# 09_Misc.net
KiCad netlist of a schematic drawn in Altium Designer
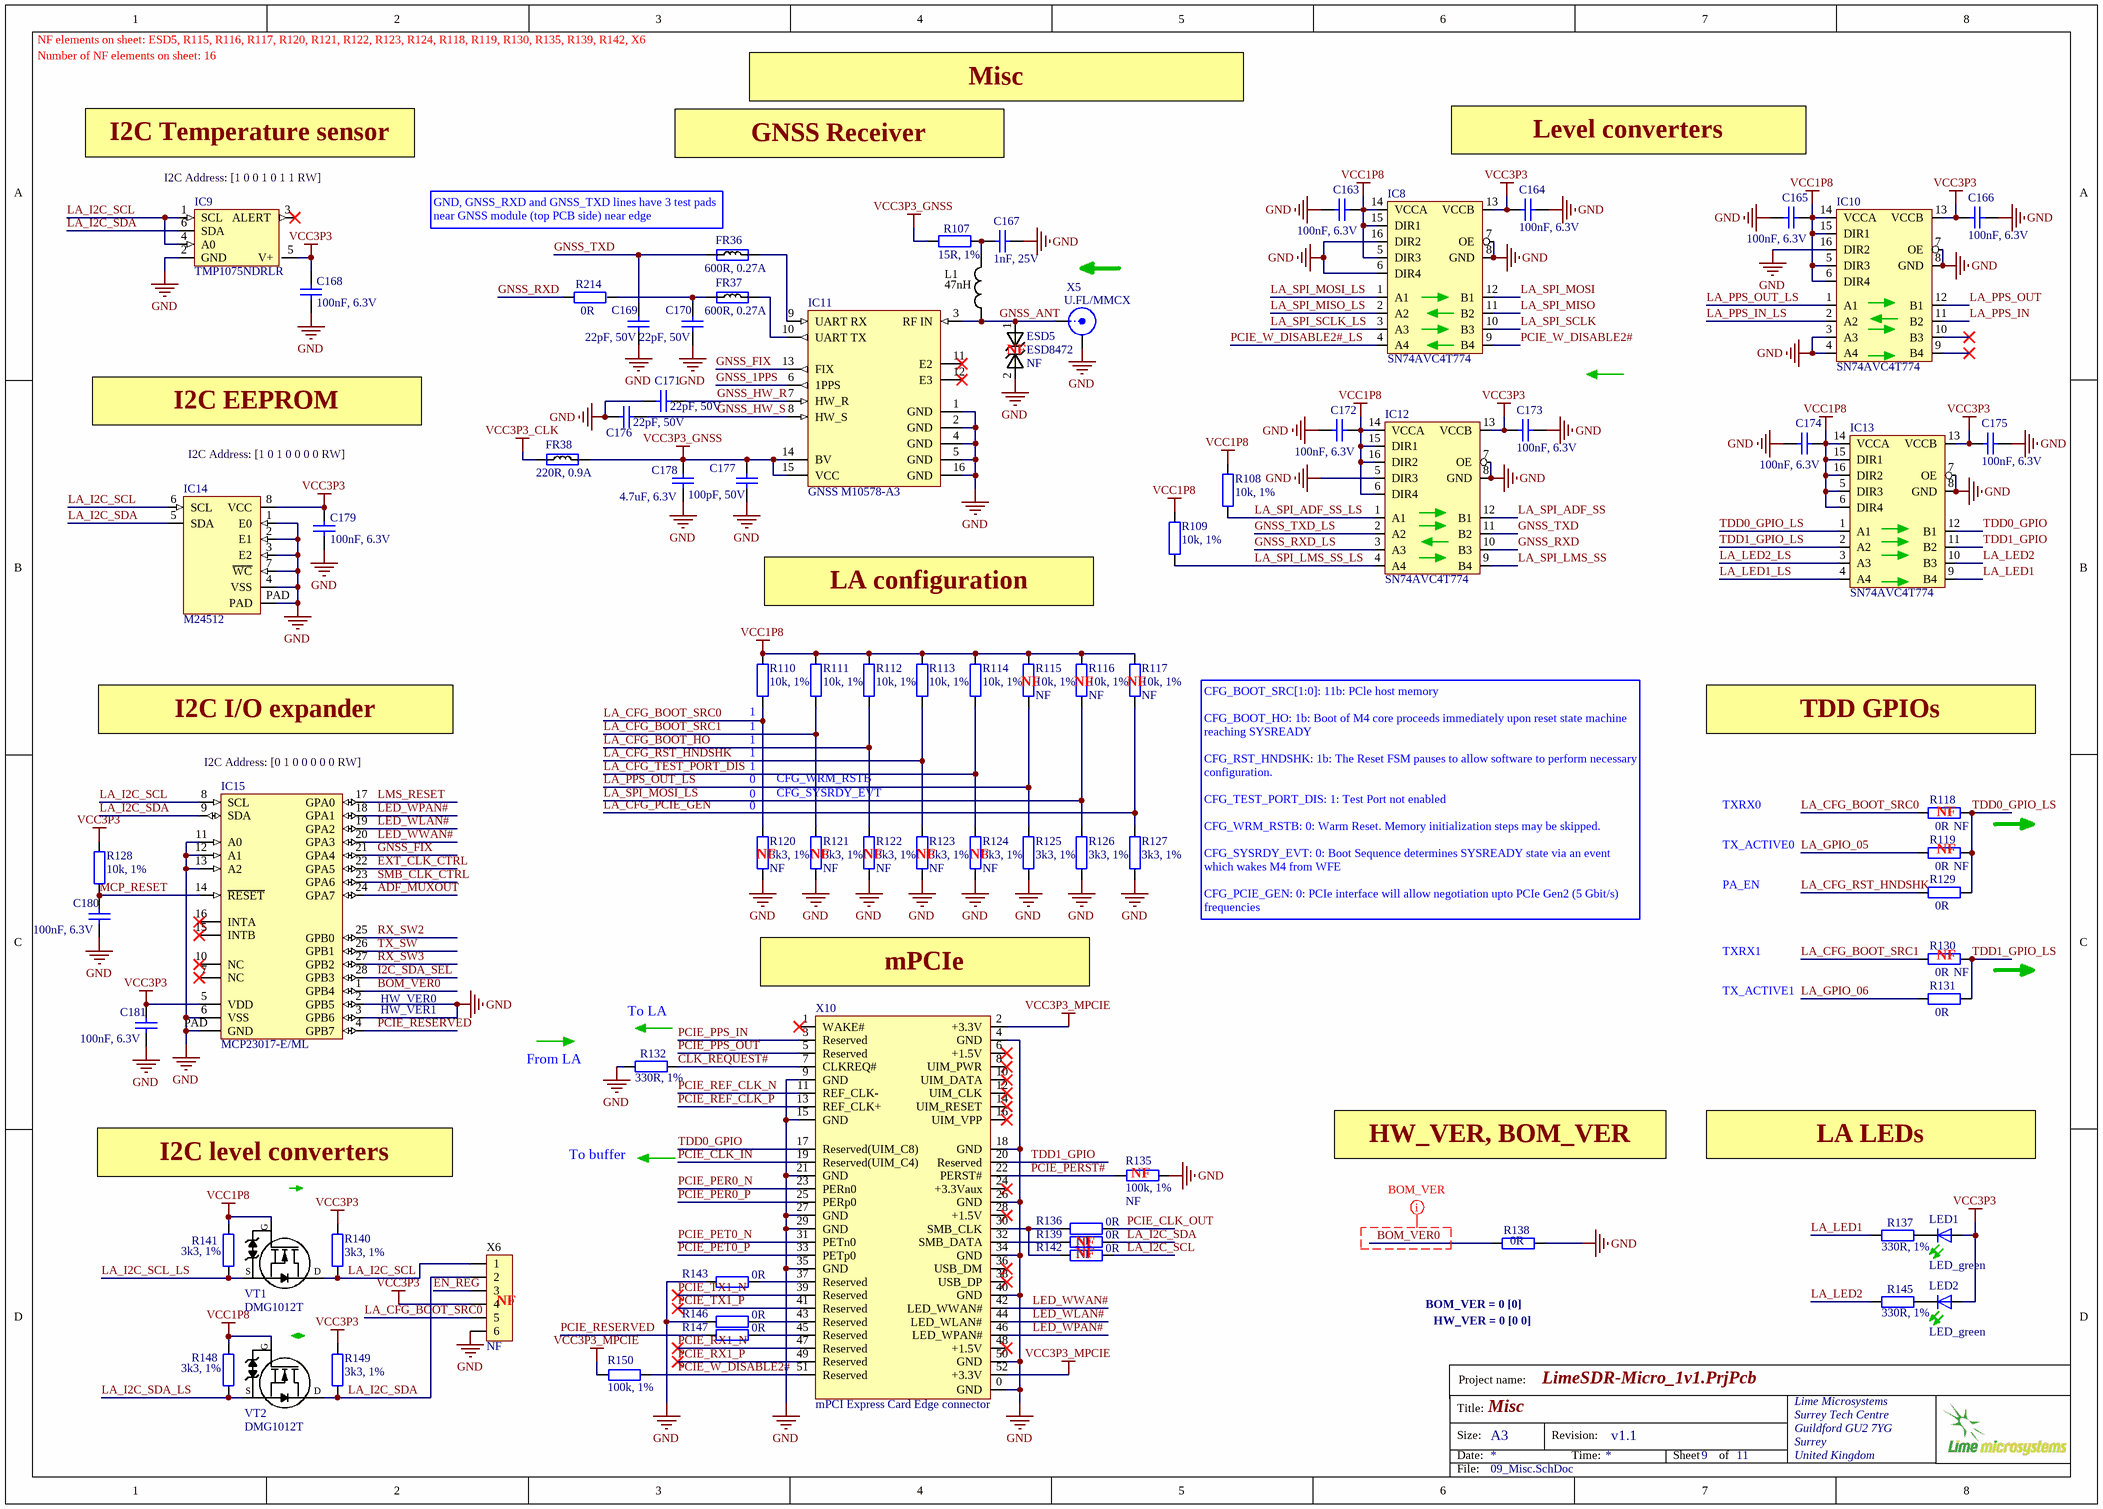
[diagram p0: 09_Misc.SchDoc]

(export (version "E")
  (design (tool "Eeschema 10.0.6"))
  (components
    (comp (ref "C163")
      (value "100nF, 6.3V")
      (footprint "CAP0201")
      (fields (field (name "MANUFACTURER") "Samsung") (field (name "TOLERANCE") "20%"))
      (libsource (lib "LimeMicroAltiumLib_schLib") (part "Cap_0402"))
    )
    (comp (ref "C164")
      (value "100nF, 6.3V")
      (footprint "CAP0201")
      (fields (field (name "MANUFACTURER") "Samsung") (field (name "TOLERANCE") "20%"))
      (libsource (lib "LimeMicroAltiumLib_schLib") (part "Cap_0402"))
    )
    (comp (ref "C165")
      (value "100nF, 6.3V")
      (footprint "CAP0201")
      (fields (field (name "MANUFACTURER") "Samsung") (field (name "TOLERANCE") "20%"))
      (libsource (lib "LimeMicroAltiumLib_schLib") (part "Cap_0402"))
    )
    (comp (ref "C166")
      (value "100nF, 6.3V")
      (footprint "CAP0201")
      (fields (field (name "MANUFACTURER") "Samsung") (field (name "TOLERANCE") "20%"))
      (libsource (lib "LimeMicroAltiumLib_schLib") (part "Cap_0402"))
    )
    (comp (ref "C167")
      (value "1nF, 25V")
      (footprint "CAP0201")
      (fields (field (name "TOLERANCE") "±10%") (field (name "MANUFACTURER") "TDK Corporation"))
      (libsource (lib "LimeMicroAltiumLib_schLib") (part "Cap_0402"))
    )
    (comp (ref "C168")
      (value "100nF, 6.3V")
      (footprint "CAP0201")
      (fields (field (name "MANUFACTURER") "Samsung") (field (name "TOLERANCE") "20%"))
      (libsource (lib "LimeMicroAltiumLib_schLib") (part "Cap_0402"))
    )
    (comp (ref "C169")
      (value "22pF, 50V")
      (footprint "CAP0201")
      (fields
        (field (name "MANUFACTURER") "Murata")
        (field (name "TOLERANCE") "5%")
        (field (name "VOLTAGE") "50V")
      )
      (libsource (lib "LimeMicroAltiumLib_schLib") (part "Cap_0402"))
    )
    (comp (ref "C170")
      (value "22pF, 50V")
      (footprint "CAP0201")
      (fields
        (field (name "MANUFACTURER") "Murata")
        (field (name "TOLERANCE") "5%")
        (field (name "VOLTAGE") "50V")
      )
      (libsource (lib "LimeMicroAltiumLib_schLib") (part "Cap_0402"))
    )
    (comp (ref "C171")
      (value "22pF, 50V")
      (footprint "CAP0201")
      (fields
        (field (name "MANUFACTURER") "Murata")
        (field (name "TOLERANCE") "5%")
        (field (name "VOLTAGE") "50V")
      )
      (libsource (lib "LimeMicroAltiumLib_schLib") (part "Cap_0402"))
    )
    (comp (ref "C172")
      (value "100nF, 6.3V")
      (footprint "CAP0201")
      (fields (field (name "MANUFACTURER") "Samsung") (field (name "TOLERANCE") "20%"))
      (libsource (lib "LimeMicroAltiumLib_schLib") (part "Cap_0402"))
    )
    (comp (ref "C173")
      (value "100nF, 6.3V")
      (footprint "CAP0201")
      (fields (field (name "MANUFACTURER") "Samsung") (field (name "TOLERANCE") "20%"))
      (libsource (lib "LimeMicroAltiumLib_schLib") (part "Cap_0402"))
    )
    (comp (ref "C174")
      (value "100nF, 6.3V")
      (footprint "CAP0201")
      (fields (field (name "MANUFACTURER") "Samsung") (field (name "TOLERANCE") "20%"))
      (libsource (lib "LimeMicroAltiumLib_schLib") (part "Cap_0402"))
    )
    (comp (ref "C175")
      (value "100nF, 6.3V")
      (footprint "CAP0201")
      (fields (field (name "MANUFACTURER") "Samsung") (field (name "TOLERANCE") "20%"))
      (libsource (lib "LimeMicroAltiumLib_schLib") (part "Cap_0402"))
    )
    (comp (ref "C176")
      (value "22pF, 50V")
      (footprint "CAP0201")
      (fields
        (field (name "MANUFACTURER") "Murata")
        (field (name "TOLERANCE") "5%")
        (field (name "VOLTAGE") "50V")
      )
      (libsource (lib "LimeMicroAltiumLib_schLib") (part "Cap_0402"))
    )
    (comp (ref "C177")
      (value "100pF, 50V")
      (footprint "CAP0201")
      (fields
        (field (name "MANUFACTURER") "TDK")
        (field (name "TOLERANCE") "5%")
        (field (name "VOLTAGE") "50V")
      )
      (libsource (lib "LimeMicroAltiumLib_schLib") (part "Cap_0402"))
    )
    (comp (ref "C178")
      (value "4.7uF, 6.3V")
      (footprint "CAP0402")
      (fields
        (field (name "MANUFACTURER") "Murata Electronics North America")
        (field (name "TOLERANCE") "±20%")
      )
      (libsource (lib "LimeMicroAltiumLib_schLib") (part "Cap_0402"))
    )
    (comp (ref "C179")
      (value "100nF, 6.3V")
      (footprint "CAP0201")
      (fields (field (name "MANUFACTURER") "Samsung") (field (name "TOLERANCE") "20%"))
      (libsource (lib "LimeMicroAltiumLib_schLib") (part "Cap_0402"))
    )
    (comp (ref "C180")
      (value "100nF, 6.3V")
      (footprint "CAP0201")
      (fields (field (name "MANUFACTURER") "Samsung") (field (name "TOLERANCE") "20%"))
      (libsource (lib "LimeMicroAltiumLib_schLib") (part "Cap_0402"))
    )
    (comp (ref "C181")
      (value "100nF, 6.3V")
      (footprint "CAP0201")
      (fields (field (name "MANUFACTURER") "Samsung") (field (name "TOLERANCE") "20%"))
      (libsource (lib "LimeMicroAltiumLib_schLib") (part "Cap_0402"))
    )
    (comp (ref "ESD5")
      (value "ESD8472")
      (footprint "ESD8472_X3DFN2")
      (fields (field (name "MANUFACTURER") "ON Semiconductor") (field (name "ASSEMBLY INFO") "NF"))
      (libsource (lib "LimeMicroAltiumLib_schLib") (part "ESD8472"))
    )
    (comp (ref "FR36")
      (value "600R, 0.27A")
      (footprint "RES0201")
      (fields (field (name "MANUFACTURER") "Taiyo Yuden"))
      (libsource (lib "LimeMicroAltiumLib_schLib") (part "Ferrite"))
    )
    (comp (ref "FR37")
      (value "600R, 0.27A")
      (footprint "RES0201")
      (fields (field (name "MANUFACTURER") "Taiyo Yuden"))
      (libsource (lib "LimeMicroAltiumLib_schLib") (part "Ferrite"))
    )
    (comp (ref "FR38")
      (value "220R, 0.9A")
      (footprint "RES0402")
      (fields (field (name "MANUFACTURER") "TDK Corporation"))
      (libsource (lib "LimeFPGAboard_schLib") (part "Ferrite"))
    )
    (comp (ref "IC8")
      (value "SN74AVC4T774")
      (footprint "SN74AVC4T774_v1")
      (fields (field (name "MANUFACTURER") "Texas Instruments"))
      (libsource (lib "LimeMicroAltiumLib") (part "SN74AVC4T774"))
    )
    (comp (ref "IC9")
      (value "TMP1075NDRLR")
      (footprint "TMP1075NDRLR_temperature_sensor_SOT563")
      (fields (field (name "MANUFACTURER") "Texas Instruments"))
      (libsource (lib "LimeMicroAltiumLib_schLib_r04") (part "TMP1075NDRLR_temperature_sensor"))
    )
    (comp (ref "IC10")
      (value "SN74AVC4T774")
      (footprint "SN74AVC4T774_v1")
      (fields (field (name "MANUFACTURER") "Texas Instruments"))
      (libsource (lib "LimeMicroAltiumLib") (part "SN74AVC4T774"))
    )
    (comp (ref "IC11")
      (value "GNSS M10578-A3")
      (footprint "M10578-A3_v2")
      (fields (field (name "MANUFACTURER") "Antenova"))
      (libsource (lib "LimeMicroAltiumLib_schLib_r04") (part "M10578-A3_GPS_GNSS"))
    )
    (comp (ref "IC12")
      (value "SN74AVC4T774")
      (footprint "SN74AVC4T774_v1")
      (fields (field (name "MANUFACTURER") "Texas Instruments"))
      (libsource (lib "LimeMicroAltiumLib") (part "SN74AVC4T774"))
    )
    (comp (ref "IC13")
      (value "SN74AVC4T774")
      (footprint "SN74AVC4T774_v1")
      (fields (field (name "MANUFACTURER") "Texas Instruments"))
      (libsource (lib "LimeMicroAltiumLib") (part "SN74AVC4T774"))
    )
    (comp (ref "IC14")
      (value "M24512")
      (footprint "M24128-DFMC6TG")
      (fields (field (name "MANUFACTURER") "STMicroelectronics"))
      (libsource (lib "LimeMicroAltiumLib_schLib") (part "M24128-DFMC6TG"))
    )
    (comp (ref "IC15")
      (value "MCP23017-E/ML")
      (footprint "MCP23017-E/ML_QFN28")
      (fields (field (name "MANUFACTURER") "Microchip"))
      (libsource (lib "LimeMicroAltiumLib") (part "MCP23017-E/ML_I2C_expander"))
    )
    (comp (ref "L1")
      (value "47nH")
      (footprint "RES0402")
      (fields
        (field (name "MANUFACTURER") "COILCRAFT")
        (field (name "MANUFACTURER PART NUMBER") "0402HP-47NXJLU")
      )
      (libsource (lib "LimeMicroAltiumLib_schLib") (part "Inductor_0603"))
    )
    (comp (ref "LED1")
      (value "LED_green")
      (footprint "LED0201")
      (fields (field (name "MANUFACTURER") "Kingbright"))
      (libsource (lib "LimeFPGAboard_schLib") (part "LED_green"))
    )
    (comp (ref "LED2")
      (value "LED_green")
      (footprint "LED0201")
      (fields (field (name "MANUFACTURER") "Kingbright"))
      (libsource (lib "LimeFPGAboard_schLib") (part "LED_green"))
    )
    (comp (ref "R107")
      (value "15R, 1%")
      (footprint "RES0201")
      (fields (field (name "MANUFACTURER") "Yageo") (field (name "TOLERANCE") "1%"))
      (libsource (lib "LimeFPGAboard_schLib") (part "Res_0402"))
    )
    (comp (ref "R108")
      (value "10k, 1%")
      (footprint "RES0201")
      (fields (field (name "MANUFACTURER") "Yageo") (field (name "TOLERANCE") "1%"))
      (libsource (lib "LimeFPGAboard_schLib") (part "Res_0402"))
    )
    (comp (ref "R109")
      (value "10k, 1%")
      (footprint "RES0201")
      (fields (field (name "MANUFACTURER") "Yageo") (field (name "TOLERANCE") "1%"))
      (libsource (lib "LimeFPGAboard_schLib") (part "Res_0402"))
    )
    (comp (ref "R110")
      (value "10k, 1%")
      (footprint "RES0201")
      (fields (field (name "MANUFACTURER") "Yageo") (field (name "TOLERANCE") "1%"))
      (libsource (lib "LimeFPGAboard_schLib") (part "Res_0402"))
    )
    (comp (ref "R111")
      (value "10k, 1%")
      (footprint "RES0201")
      (fields (field (name "MANUFACTURER") "Yageo") (field (name "TOLERANCE") "1%"))
      (libsource (lib "LimeFPGAboard_schLib") (part "Res_0402"))
    )
    (comp (ref "R112")
      (value "10k, 1%")
      (footprint "RES0201")
      (fields (field (name "MANUFACTURER") "Yageo") (field (name "TOLERANCE") "1%"))
      (libsource (lib "LimeFPGAboard_schLib") (part "Res_0402"))
    )
    (comp (ref "R113")
      (value "10k, 1%")
      (footprint "RES0201")
      (fields (field (name "MANUFACTURER") "Yageo") (field (name "TOLERANCE") "1%"))
      (libsource (lib "LimeFPGAboard_schLib") (part "Res_0402"))
    )
    (comp (ref "R114")
      (value "10k, 1%")
      (footprint "RES0201")
      (fields (field (name "MANUFACTURER") "Yageo") (field (name "TOLERANCE") "1%"))
      (libsource (lib "LimeFPGAboard_schLib") (part "Res_0402"))
    )
    (comp (ref "R115")
      (value "10k, 1%")
      (footprint "RES0201")
      (fields
        (field (name "ASSEMBLY INFO") "NF")
        (field (name "MANUFACTURER") "Yageo")
        (field (name "TOLERANCE") "1%")
      )
      (libsource (lib "LimeFPGAboard_schLib") (part "Res_0402"))
    )
    (comp (ref "R116")
      (value "10k, 1%")
      (footprint "RES0201")
      (fields
        (field (name "ASSEMBLY INFO") "NF")
        (field (name "MANUFACTURER") "Yageo")
        (field (name "TOLERANCE") "1%")
      )
      (libsource (lib "LimeFPGAboard_schLib") (part "Res_0402"))
    )
    (comp (ref "R117")
      (value "10k, 1%")
      (footprint "RES0201")
      (fields
        (field (name "ASSEMBLY INFO") "NF")
        (field (name "MANUFACTURER") "Yageo")
        (field (name "TOLERANCE") "1%")
      )
      (libsource (lib "LimeFPGAboard_schLib") (part "Res_0402"))
    )
    (comp (ref "R118")
      (value "0R")
      (footprint "RES0201")
      (fields
        (field (name "ASSEMBLY INFO") "NF")
        (field (name "MANUFACTURER") "Yageo")
        (field (name "TOLERANCE") "5%")
      )
      (libsource (lib "LimeFPGAboard_schLib") (part "Res_0402"))
    )
    (comp (ref "R119")
      (value "0R")
      (footprint "RES0201")
      (fields
        (field (name "ASSEMBLY INFO") "NF")
        (field (name "MANUFACTURER") "Yageo")
        (field (name "TOLERANCE") "5%")
      )
      (libsource (lib "LimeFPGAboard_schLib") (part "Res_0402"))
    )
    (comp (ref "R120")
      (value "3k3, 1%")
      (footprint "RES0201")
      (fields
        (field (name "ASSEMBLY INFO") "NF")
        (field (name "MANUFACTURER") "Yageo")
        (field (name "TOLERANCE") "1%")
      )
      (libsource (lib "LimeFPGAboard_schLib") (part "Res_0402"))
    )
    (comp (ref "R121")
      (value "3k3, 1%")
      (footprint "RES0201")
      (fields
        (field (name "ASSEMBLY INFO") "NF")
        (field (name "MANUFACTURER") "Yageo")
        (field (name "TOLERANCE") "1%")
      )
      (libsource (lib "LimeFPGAboard_schLib") (part "Res_0402"))
    )
    (comp (ref "R122")
      (value "3k3, 1%")
      (footprint "RES0201")
      (fields
        (field (name "ASSEMBLY INFO") "NF")
        (field (name "MANUFACTURER") "Yageo")
        (field (name "TOLERANCE") "1%")
      )
      (libsource (lib "LimeFPGAboard_schLib") (part "Res_0402"))
    )
    (comp (ref "R123")
      (value "3k3, 1%")
      (footprint "RES0201")
      (fields
        (field (name "ASSEMBLY INFO") "NF")
        (field (name "MANUFACTURER") "Yageo")
        (field (name "TOLERANCE") "1%")
      )
      (libsource (lib "LimeFPGAboard_schLib") (part "Res_0402"))
    )
    (comp (ref "R124")
      (value "3k3, 1%")
      (footprint "RES0201")
      (fields
        (field (name "ASSEMBLY INFO") "NF")
        (field (name "MANUFACTURER") "Yageo")
        (field (name "TOLERANCE") "1%")
      )
      (libsource (lib "LimeFPGAboard_schLib") (part "Res_0402"))
    )
    (comp (ref "R125")
      (value "3k3, 1%")
      (footprint "RES0201")
      (fields (field (name "MANUFACTURER") "Yageo") (field (name "TOLERANCE") "1%"))
      (libsource (lib "LimeFPGAboard_schLib") (part "Res_0402"))
    )
    (comp (ref "R126")
      (value "3k3, 1%")
      (footprint "RES0201")
      (fields (field (name "MANUFACTURER") "Yageo") (field (name "TOLERANCE") "1%"))
      (libsource (lib "LimeFPGAboard_schLib") (part "Res_0402"))
    )
    (comp (ref "R127")
      (value "3k3, 1%")
      (footprint "RES0201")
      (fields (field (name "MANUFACTURER") "Yageo") (field (name "TOLERANCE") "1%"))
      (libsource (lib "LimeFPGAboard_schLib") (part "Res_0402"))
    )
    (comp (ref "R128")
      (value "10k, 1%")
      (footprint "RES0201")
      (fields (field (name "MANUFACTURER") "Yageo") (field (name "TOLERANCE") "1%"))
      (libsource (lib "LimeFPGAboard_schLib") (part "Res_0402"))
    )
    (comp (ref "R129")
      (value "0R")
      (footprint "RES0201")
      (fields (field (name "MANUFACTURER") "Yageo") (field (name "TOLERANCE") "5%"))
      (libsource (lib "LimeFPGAboard_schLib") (part "Res_0402"))
    )
    (comp (ref "R130")
      (value "0R")
      (footprint "RES0201")
      (fields
        (field (name "ASSEMBLY INFO") "NF")
        (field (name "MANUFACTURER") "Yageo")
        (field (name "TOLERANCE") "5%")
      )
      (libsource (lib "LimeFPGAboard_schLib") (part "Res_0402"))
    )
    (comp (ref "R131")
      (value "0R")
      (footprint "RES0201")
      (fields (field (name "MANUFACTURER") "Yageo") (field (name "TOLERANCE") "5%"))
      (libsource (lib "LimeFPGAboard_schLib") (part "Res_0402"))
    )
    (comp (ref "R132")
      (value "330R, 1%")
      (footprint "RES0201")
      (fields (field (name "MANUFACTURER") "Vishay Dale") (field (name "TOLERANCE") "1%"))
      (libsource (lib "LimeFPGAboard_schLib") (part "Res_0402"))
    )
    (comp (ref "R135")
      (value "100k, 1%")
      (footprint "RES0201")
      (fields
        (field (name "ASSEMBLY INFO") "NF")
        (field (name "MANUFACTURER") "Yageo")
        (field (name "TOLERANCE") "1%")
      )
      (libsource (lib "LimeMicroAltiumLib_schLib") (part "Res_0402"))
    )
    (comp (ref "R136")
      (value "0R")
      (footprint "RES0201")
      (fields (field (name "MANUFACTURER") "Yageo") (field (name "TOLERANCE") "5%"))
      (libsource (lib "LimeFPGAboard_schLib") (part "Res_0402"))
    )
    (comp (ref "R137")
      (value "330R, 1%")
      (footprint "RES0201")
      (fields (field (name "MANUFACTURER") "Vishay Dale") (field (name "TOLERANCE") "1%"))
      (libsource (lib "LimeFPGAboard_schLib") (part "Res_0402"))
    )
    (comp (ref "R138")
      (value "0R")
      (footprint "RES0201")
      (fields (field (name "MANUFACTURER") "Yageo") (field (name "TOLERANCE") "5%"))
      (libsource (lib "LimeFPGAboard_schLib") (part "Res_0402"))
    )
    (comp (ref "R139")
      (value "0R")
      (footprint "RES0201")
      (fields
        (field (name "ASSEMBLY INFO") "NF")
        (field (name "MANUFACTURER") "Yageo")
        (field (name "TOLERANCE") "5%")
      )
      (libsource (lib "LimeFPGAboard_schLib") (part "Res_0402"))
    )
    (comp (ref "R140")
      (value "3k3, 1%")
      (footprint "RES0201")
      (fields (field (name "MANUFACTURER") "Yageo") (field (name "TOLERANCE") "1%"))
      (libsource (lib "LimeFPGAboard_schLib") (part "Res_0402"))
    )
    (comp (ref "R141")
      (value "3k3, 1%")
      (footprint "RES0201")
      (fields (field (name "MANUFACTURER") "Yageo") (field (name "TOLERANCE") "1%"))
      (libsource (lib "LimeFPGAboard_schLib") (part "Res_0402"))
    )
    (comp (ref "R142")
      (value "0R")
      (footprint "RES0201")
      (fields
        (field (name "ASSEMBLY INFO") "NF")
        (field (name "MANUFACTURER") "Yageo")
        (field (name "TOLERANCE") "5%")
      )
      (libsource (lib "LimeFPGAboard_schLib") (part "Res_0402"))
    )
    (comp (ref "R143")
      (value "0R")
      (footprint "RES0201")
      (fields (field (name "MANUFACTURER") "Yageo") (field (name "TOLERANCE") "5%"))
      (libsource (lib "LimeFPGAboard_schLib") (part "Res_0402"))
    )
    (comp (ref "R145")
      (value "330R, 1%")
      (footprint "RES0201")
      (fields (field (name "MANUFACTURER") "Vishay Dale") (field (name "TOLERANCE") "1%"))
      (libsource (lib "LimeFPGAboard_schLib") (part "Res_0402"))
    )
    (comp (ref "R146")
      (value "0R")
      (footprint "RES0201")
      (fields (field (name "MANUFACTURER") "Yageo") (field (name "TOLERANCE") "5%"))
      (libsource (lib "LimeFPGAboard_schLib") (part "Res_0402"))
    )
    (comp (ref "R147")
      (value "0R")
      (footprint "RES0201")
      (fields (field (name "MANUFACTURER") "Yageo") (field (name "TOLERANCE") "5%"))
      (libsource (lib "LimeFPGAboard_schLib") (part "Res_0402"))
    )
    (comp (ref "R148")
      (value "3k3, 1%")
      (footprint "RES0201")
      (fields (field (name "MANUFACTURER") "Yageo") (field (name "TOLERANCE") "1%"))
      (libsource (lib "LimeFPGAboard_schLib") (part "Res_0402"))
    )
    (comp (ref "R149")
      (value "3k3, 1%")
      (footprint "RES0201")
      (fields (field (name "MANUFACTURER") "Yageo") (field (name "TOLERANCE") "1%"))
      (libsource (lib "LimeFPGAboard_schLib") (part "Res_0402"))
    )
    (comp (ref "R150")
      (value "100k, 1%")
      (footprint "RES0201")
      (fields (field (name "MANUFACTURER") "Yageo") (field (name "TOLERANCE") "1%"))
      (libsource (lib "LimeMicroAltiumLib_schLib") (part "Res_0402"))
    )
    (comp (ref "R214")
      (value "0R")
      (footprint "RES0201")
      (fields (field (name "MANUFACTURER") "Yageo") (field (name "TOLERANCE") "5%"))
      (libsource (lib "LimeFPGAboard_schLib") (part "Res_0402"))
    )
    (comp (ref "VT1")
      (value "DMG1012T")
      (footprint "SOT523")
      (fields (field (name "MANUFACTURER") "Diodes Incorporated"))
      (libsource (lib "LimeMicroAltiumLib_schLib_r01") (part "DMG1012T"))
    )
    (comp (ref "VT2")
      (value "DMG1012T")
      (footprint "SOT523")
      (fields (field (name "MANUFACTURER") "Diodes Incorporated"))
      (libsource (lib "LimeMicroAltiumLib_schLib_r01") (part "DMG1012T"))
    )
    (comp (ref "X5")
      (value "U.FL/MMCX")
      (footprint "MMCX_UFL_conn_u_v2")
      (description "CONN UMC RCPT STR 50 OHM SMD")
      (fields (field (name "MANUFACTURER") "Molex, LLC"))
      (libsource (lib "LimeMicroAltiumLib_schLib") (part "RF_IF_connector"))
    )
    (comp (ref "X6")
      (value "Molex 0788641001")
      (footprint "Molex_0788641001_spring_contacts")
      (description "Header, 6-pin")
      (fields (field (name "MANUFACTURER") "Molex") (field (name "ASSEMBLY INFO") "NF"))
      (libsource (lib "LimeMicroAltiumLib_schLib_r04") (part "Molex_0788641001_spring_contacts"))
    )
    (comp (ref "X10")
      (value "mPCI Express Card Edge connector")
      (footprint "PCIe_MiniCard")
      (description "PCIe MiniCard full or half size")
      (libsource (lib "LimeMicroAltiumLib_schLib_r04") (part "PCIe_MiniCard_fingers"))
    )
  )
  (nets
    (net (code "1") (name "/ADF_MUXOUT") (class "Default")
      (node (ref "IC15") (pin "24") (pinfunction "GPA7_24") (pintype "bidirectional"))
    )
    (net (code "2") (name "/BOM_VER0") (class "Default")
      (node (ref "IC15") (pin "1") (pinfunction "GPB4_1") (pintype "bidirectional"))
      (node (ref "R138") (pin "1") (pinfunction "1_1") (pintype "passive"))
    )
    (net (code "3") (name "/CLK_REQUEST#") (class "Default")
      (node (ref "R132") (pin "1") (pinfunction "1_1") (pintype "passive"))
      (node (ref "X10") (pin "7") (pinfunction "CLKREQ#_7") (pintype "passive"))
    )
    (net (code "4") (name "/EN_REG") (class "Default")
      (node (ref "X6") (pin "3") (pinfunction "3_3") (pintype "passive"))
    )
    (net (code "5") (name "/EXT_CLK_CTRL") (class "Default")
      (node (ref "IC15") (pin "22") (pinfunction "GPA5_22") (pintype "bidirectional"))
    )
    (net (code "6") (name "/GNSS_1PPS") (class "Default")
      (node (ref "IC11") (pin "6") (pinfunction "1PPS_6") (pintype "output"))
    )
    (net (code "7") (name "/GNSS_ANT") (class "Default")
      (node (ref "ESD5") (pin "1") (pinfunction "1_1") (pintype "passive"))
      (node (ref "IC11") (pin "3") (pinfunction "RF_IN_3") (pintype "input"))
      (node (ref "L1") (pin "1") (pinfunction "1_1") (pintype "passive"))
      (node (ref "X5") (pin "1") (pinfunction "X_1") (pintype "passive"))
    )
    (net (code "8") (name "/GNSS_FIX") (class "Default")
      (node (ref "IC11") (pin "13") (pinfunction "FIX_13") (pintype "output"))
      (node (ref "IC15") (pin "21") (pinfunction "GPA4_21") (pintype "bidirectional"))
    )
    (net (code "9") (name "/GNSS_HW_R") (class "Default")
      (node (ref "C171") (pin "1") (pinfunction "1_1") (pintype "passive"))
      (node (ref "IC11") (pin "7") (pinfunction "HW_R_7") (pintype "input"))
    )
    (net (code "10") (name "/GNSS_HW_S") (class "Default")
      (node (ref "C176") (pin "1") (pinfunction "1_1") (pintype "passive"))
      (node (ref "IC11") (pin "8") (pinfunction "HW_S_8") (pintype "input"))
    )
    (net (code "11") (name "/GNSS_RXD") (class "Default")
      (node (ref "IC12") (pin "10") (pinfunction "B3_10") (pintype "passive"))
      (node (ref "R214") (pin "1") (pinfunction "1_1") (pintype "passive"))
    )
    (net (code "12") (name "/GNSS_RXD_LS") (class "Default")
      (node (ref "IC12") (pin "3") (pinfunction "A3_3") (pintype "passive"))
    )
    (net (code "13") (name "/GNSS_TXD") (class "Default")
      (node (ref "C169") (pin "1") (pinfunction "1_1") (pintype "passive"))
      (node (ref "FR36") (pin "1") (pinfunction "1_1") (pintype "passive"))
      (node (ref "IC12") (pin "11") (pinfunction "B2_11") (pintype "passive"))
    )
    (net (code "14") (name "/GNSS_TXD_LS") (class "Default")
      (node (ref "IC12") (pin "2") (pinfunction "A2_2") (pintype "passive"))
    )
    (net (code "15") (name "/I2C_SDA_SEL") (class "Default")
      (node (ref "IC15") (pin "28") (pinfunction "GPB3_28") (pintype "bidirectional"))
    )
    (net (code "16") (name "/LA_CFG_BOOT_HO") (class "Default")
      (node (ref "R112") (pin "2") (pinfunction "2_2") (pintype "passive"))
      (node (ref "R122") (pin "1") (pinfunction "1_1") (pintype "passive"))
    )
    (net (code "17") (name "/LA_CFG_BOOT_SRC0") (class "Default")
      (node (ref "R110") (pin "2") (pinfunction "2_2") (pintype "passive"))
      (node (ref "R118") (pin "1") (pinfunction "1_1") (pintype "passive"))
      (node (ref "R120") (pin "1") (pinfunction "1_1") (pintype "passive"))
      (node (ref "X6") (pin "5") (pinfunction "5_5") (pintype "passive"))
    )
    (net (code "18") (name "/LA_CFG_BOOT_SRC1") (class "Default")
      (node (ref "R111") (pin "2") (pinfunction "2_2") (pintype "passive"))
      (node (ref "R121") (pin "1") (pinfunction "1_1") (pintype "passive"))
      (node (ref "R130") (pin "1") (pinfunction "1_1") (pintype "passive"))
    )
    (net (code "19") (name "/LA_CFG_PCIE_GEN") (class "Default")
      (node (ref "R117") (pin "2") (pinfunction "2_2") (pintype "passive"))
      (node (ref "R127") (pin "1") (pinfunction "1_1") (pintype "passive"))
    )
    (net (code "20") (name "/LA_CFG_RST_HNDSHK") (class "Default")
      (node (ref "R113") (pin "2") (pinfunction "2_2") (pintype "passive"))
      (node (ref "R123") (pin "1") (pinfunction "1_1") (pintype "passive"))
      (node (ref "R129") (pin "1") (pinfunction "1_1") (pintype "passive"))
    )
    (net (code "21") (name "/LA_CFG_TEST_PORT_DIS") (class "Default")
      (node (ref "R114") (pin "2") (pinfunction "2_2") (pintype "passive"))
      (node (ref "R124") (pin "1") (pinfunction "1_1") (pintype "passive"))
    )
    (net (code "22") (name "/LA_GPIO_05") (class "Default")
      (node (ref "R119") (pin "1") (pinfunction "1_1") (pintype "passive"))
    )
    (net (code "23") (name "/LA_GPIO_06") (class "Default")
      (node (ref "R131") (pin "1") (pinfunction "1_1") (pintype "passive"))
    )
    (net (code "24") (name "/LA_I2C_SCL") (class "Default")
      (node (ref "IC14") (pin "6") (pinfunction "SCL_6") (pintype "input"))
      (node (ref "IC15") (pin "8") (pinfunction "SCL_8") (pintype "input"))
      (node (ref "IC9") (pin "1") (pinfunction "SCL_1") (pintype "input"))
      (node (ref "IC9") (pin "4") (pinfunction "A0_4") (pintype "input"))
      (node (ref "R140") (pin "2") (pinfunction "2_2") (pintype "passive"))
      (node (ref "R142") (pin "2") (pinfunction "2_2") (pintype "passive"))
      (node (ref "VT1") (pin "D") (pinfunction "D_D") (pintype "passive"))
      (node (ref "X6") (pin "1") (pinfunction "1_1") (pintype "passive"))
    )
    (net (code "25") (name "/LA_I2C_SCL_LS") (class "Default")
      (node (ref "R141") (pin "2") (pinfunction "2_2") (pintype "passive"))
      (node (ref "VT1") (pin "S") (pinfunction "S_S") (pintype "passive"))
    )
    (net (code "26") (name "/LA_I2C_SDA") (class "Default")
      (node (ref "IC14") (pin "5") (pinfunction "SDA_5") (pintype "bidirectional"))
      (node (ref "IC15") (pin "9") (pinfunction "SDA_9") (pintype "bidirectional"))
      (node (ref "IC9") (pin "6") (pinfunction "SDA_6") (pintype "bidirectional"))
      (node (ref "R139") (pin "2") (pinfunction "2_2") (pintype "passive"))
      (node (ref "R149") (pin "2") (pinfunction "2_2") (pintype "passive"))
      (node (ref "VT2") (pin "D") (pinfunction "D_D") (pintype "passive"))
      (node (ref "X6") (pin "2") (pinfunction "2_2") (pintype "passive"))
    )
    (net (code "27") (name "/LA_I2C_SDA_LS") (class "Default")
      (node (ref "R148") (pin "2") (pinfunction "2_2") (pintype "passive"))
      (node (ref "VT2") (pin "S") (pinfunction "S_S") (pintype "passive"))
    )
    (net (code "28") (name "/LA_LED1") (class "Default")
      (node (ref "IC13") (pin "9") (pinfunction "B4_9") (pintype "passive"))
      (node (ref "R137") (pin "2") (pinfunction "2_2") (pintype "passive"))
    )
    (net (code "29") (name "/LA_LED1_LS") (class "Default")
      (node (ref "IC13") (pin "4") (pinfunction "A4_4") (pintype "passive"))
    )
    (net (code "30") (name "/LA_LED2") (class "Default")
      (node (ref "IC13") (pin "10") (pinfunction "B3_10") (pintype "passive"))
      (node (ref "R145") (pin "2") (pinfunction "2_2") (pintype "passive"))
    )
    (net (code "31") (name "/LA_LED2_LS") (class "Default")
      (node (ref "IC13") (pin "3") (pinfunction "A3_3") (pintype "passive"))
    )
    (net (code "32") (name "/LA_PPS_IN") (class "Default")
      (node (ref "IC10") (pin "11") (pinfunction "B2_11") (pintype "passive"))
    )
    (net (code "33") (name "/LA_PPS_IN_LS") (class "Default")
      (node (ref "IC10") (pin "2") (pinfunction "A2_2") (pintype "passive"))
    )
    (net (code "34") (name "/LA_PPS_OUT") (class "Default")
      (node (ref "IC10") (pin "12") (pinfunction "B1_12") (pintype "passive"))
    )
    (net (code "35") (name "/LA_PPS_OUT_LS") (class "Default")
      (node (ref "IC10") (pin "1") (pinfunction "A1_1") (pintype "passive"))
      (node (ref "R115") (pin "2") (pinfunction "2_2") (pintype "passive"))
      (node (ref "R125") (pin "1") (pinfunction "1_1") (pintype "passive"))
    )
    (net (code "36") (name "/LA_SPI_ADF_SS") (class "Default")
      (node (ref "IC12") (pin "12") (pinfunction "B1_12") (pintype "passive"))
    )
    (net (code "37") (name "/LA_SPI_ADF_SS_LS") (class "Default")
      (node (ref "IC12") (pin "1") (pinfunction "A1_1") (pintype "passive"))
      (node (ref "R108") (pin "2") (pinfunction "2_2") (pintype "passive"))
    )
    (net (code "38") (name "/LA_SPI_LMS_SS") (class "Default")
      (node (ref "IC12") (pin "9") (pinfunction "B4_9") (pintype "passive"))
    )
    (net (code "39") (name "/LA_SPI_LMS_SS_LS") (class "Default")
      (node (ref "IC12") (pin "4") (pinfunction "A4_4") (pintype "passive"))
      (node (ref "R109") (pin "2") (pinfunction "2_2") (pintype "passive"))
    )
    (net (code "40") (name "/LA_SPI_MISO") (class "Default")
      (node (ref "IC8") (pin "11") (pinfunction "B2_11") (pintype "passive"))
    )
    (net (code "41") (name "/LA_SPI_MISO_LS") (class "Default")
      (node (ref "IC8") (pin "2") (pinfunction "A2_2") (pintype "passive"))
    )
    (net (code "42") (name "/LA_SPI_MOSI") (class "Default")
      (node (ref "IC8") (pin "12") (pinfunction "B1_12") (pintype "passive"))
    )
    (net (code "43") (name "/LA_SPI_MOSI_LS") (class "Default")
      (node (ref "IC8") (pin "1") (pinfunction "A1_1") (pintype "passive"))
      (node (ref "R116") (pin "2") (pinfunction "2_2") (pintype "passive"))
      (node (ref "R126") (pin "1") (pinfunction "1_1") (pintype "passive"))
    )
    (net (code "44") (name "/LA_SPI_SCLK") (class "Default")
      (node (ref "IC8") (pin "10") (pinfunction "B3_10") (pintype "passive"))
    )
    (net (code "45") (name "/LA_SPI_SCLK_LS") (class "Default")
      (node (ref "IC8") (pin "3") (pinfunction "A3_3") (pintype "passive"))
    )
    (net (code "46") (name "/LED_WLAN#") (class "Default")
      (node (ref "IC15") (pin "19") (pinfunction "GPA2_19") (pintype "bidirectional"))
      (node (ref "X10") (pin "44") (pinfunction "LED_WLAN#_44") (pintype "passive"))
    )
    (net (code "47") (name "/LED_WPAN#") (class "Default")
      (node (ref "IC15") (pin "18") (pinfunction "GPA1_18") (pintype "bidirectional"))
      (node (ref "X10") (pin "46") (pinfunction "LED_WPAN#_46") (pintype "passive"))
    )
    (net (code "48") (name "/LED_WWAN#") (class "Default")
      (node (ref "IC15") (pin "20") (pinfunction "GPA3_20") (pintype "bidirectional"))
      (node (ref "X10") (pin "42") (pinfunction "LED_WWAN#_42") (pintype "passive"))
    )
    (net (code "49") (name "/LMS_RESET") (class "Default")
      (node (ref "IC15") (pin "17") (pinfunction "GPA0_17") (pintype "bidirectional"))
    )
    (net (code "50") (name "/MCP_RESET") (class "Default")
      (node (ref "C180") (pin "1") (pinfunction "1_1") (pintype "passive"))
      (node (ref "IC15") (pin "14") (pinfunction "~{RESET}_14") (pintype "input"))
      (node (ref "R128") (pin "2") (pinfunction "2_2") (pintype "passive"))
    )
    (net (code "51") (name "/PCIE_CLK_IN") (class "Default")
      (node (ref "X10") (pin "19") (pinfunction "Reserved(UIM_C4)_19") (pintype "passive"))
    )
    (net (code "52") (name "/PCIE_CLK_OUT") (class "Default")
      (node (ref "R136") (pin "2") (pinfunction "2_2") (pintype "passive"))
    )
    (net (code "53") (name "/PCIE_PER0_N") (class "Default")
      (node (ref "X10") (pin "23") (pinfunction "PERn0_23") (pintype "passive"))
    )
    (net (code "54") (name "/PCIE_PER0_P") (class "Default")
      (node (ref "X10") (pin "25") (pinfunction "PERp0_25") (pintype "passive"))
    )
    (net (code "55") (name "/PCIE_PERST#") (class "Default")
      (node (ref "R135") (pin "2") (pinfunction "2_2") (pintype "passive"))
      (node (ref "X10") (pin "22") (pinfunction "PERST#_22") (pintype "passive"))
    )
    (net (code "56") (name "/PCIE_PET0_N") (class "Default")
      (node (ref "X10") (pin "31") (pinfunction "PETn0_31") (pintype "passive"))
    )
    (net (code "57") (name "/PCIE_PET0_P") (class "Default")
      (node (ref "X10") (pin "33") (pinfunction "PETp0_33") (pintype "passive"))
    )
    (net (code "58") (name "/PCIE_PPS_IN") (class "Default")
      (node (ref "X10") (pin "3") (pinfunction "Reserved_3") (pintype "passive"))
    )
    (net (code "59") (name "/PCIE_PPS_OUT") (class "Default")
      (node (ref "X10") (pin "5") (pinfunction "Reserved_5") (pintype "passive"))
    )
    (net (code "60") (name "/PCIE_REF_CLK_N") (class "Default")
      (node (ref "X10") (pin "11") (pinfunction "REF_CLK-_11") (pintype "passive"))
    )
    (net (code "61") (name "/PCIE_REF_CLK_P") (class "Default")
      (node (ref "X10") (pin "13") (pinfunction "REF_CLK+_13") (pintype "passive"))
    )
    (net (code "62") (name "/PCIE_RESERVED") (class "Default")
      (node (ref "IC15") (pin "4") (pinfunction "GPB7_4") (pintype "bidirectional"))
      (node (ref "R147") (pin "1") (pinfunction "1_1") (pintype "passive"))
    )
    (net (code "63") (name "/PCIE_RX1_N") (class "Default")
      (node (ref "X10") (pin "47") (pinfunction "Reserved_47") (pintype "passive+no_connect"))
    )
    (net (code "64") (name "/PCIE_RX1_P") (class "Default")
      (node (ref "X10") (pin "49") (pinfunction "Reserved_49") (pintype "passive+no_connect"))
    )
    (net (code "65") (name "/PCIE_TX1_N") (class "Default")
      (node (ref "X10") (pin "39") (pinfunction "Reserved_39") (pintype "passive+no_connect"))
    )
    (net (code "66") (name "/PCIE_TX1_P") (class "Default")
      (node (ref "X10") (pin "41") (pinfunction "Reserved_41") (pintype "passive+no_connect"))
    )
    (net (code "67") (name "/PCIE_W_DISABLE2#") (class "Default")
      (node (ref "IC8") (pin "9") (pinfunction "B4_9") (pintype "passive"))
      (node (ref "R150") (pin "1") (pinfunction "1_1") (pintype "passive"))
      (node (ref "X10") (pin "51") (pinfunction "Reserved_51") (pintype "passive"))
    )
    (net (code "68") (name "/PCIE_W_DISABLE2#_LS") (class "Default")
      (node (ref "IC8") (pin "4") (pinfunction "A4_4") (pintype "passive"))
    )
    (net (code "69") (name "/RX_SW2") (class "Default")
      (node (ref "IC15") (pin "25") (pinfunction "GPB0_25") (pintype "bidirectional"))
    )
    (net (code "70") (name "/RX_SW3") (class "Default")
      (node (ref "IC15") (pin "27") (pinfunction "GPB2_27") (pintype "bidirectional"))
    )
    (net (code "71") (name "/SMB_CLK_CTRL") (class "Default")
      (node (ref "IC15") (pin "23") (pinfunction "GPA6_23") (pintype "bidirectional"))
    )
    (net (code "72") (name "/TDD0_GPIO") (class "Default")
      (node (ref "IC13") (pin "12") (pinfunction "B1_12") (pintype "passive"))
      (node (ref "X10") (pin "17") (pinfunction "Reserved(UIM_C8)_17") (pintype "passive"))
    )
    (net (code "73") (name "/TDD0_GPIO_LS") (class "Default")
      (node (ref "IC13") (pin "1") (pinfunction "A1_1") (pintype "passive"))
      (node (ref "R118") (pin "2") (pinfunction "2_2") (pintype "passive"))
      (node (ref "R119") (pin "2") (pinfunction "2_2") (pintype "passive"))
      (node (ref "R129") (pin "2") (pinfunction "2_2") (pintype "passive"))
    )
    (net (code "74") (name "/TDD1_GPIO") (class "Default")
      (node (ref "IC13") (pin "11") (pinfunction "B2_11") (pintype "passive"))
      (node (ref "X10") (pin "20") (pinfunction "Reserved_20") (pintype "passive"))
    )
    (net (code "75") (name "/TDD1_GPIO_LS") (class "Default")
      (node (ref "IC13") (pin "2") (pinfunction "A2_2") (pintype "passive"))
      (node (ref "R130") (pin "2") (pinfunction "2_2") (pintype "passive"))
      (node (ref "R131") (pin "2") (pinfunction "2_2") (pintype "passive"))
    )
    (net (code "76") (name "/TX_SW") (class "Default")
      (node (ref "IC15") (pin "26") (pinfunction "GPB1_26") (pintype "bidirectional"))
    )
    (net (code "77") (name "GND") (class "Default")
      (node (ref "C163") (pin "1") (pinfunction "1_1") (pintype "passive"))
      (node (ref "C164") (pin "2") (pinfunction "2_2") (pintype "passive"))
      (node (ref "C165") (pin "1") (pinfunction "1_1") (pintype "passive"))
      (node (ref "C166") (pin "2") (pinfunction "2_2") (pintype "passive"))
      (node (ref "C167") (pin "2") (pinfunction "2_2") (pintype "passive"))
      (node (ref "C168") (pin "2") (pinfunction "2_2") (pintype "passive"))
      (node (ref "C169") (pin "2") (pinfunction "2_2") (pintype "passive"))
      (node (ref "C170") (pin "2") (pinfunction "2_2") (pintype "passive"))
      (node (ref "C171") (pin "2") (pinfunction "2_2") (pintype "passive"))
      (node (ref "C172") (pin "1") (pinfunction "1_1") (pintype "passive"))
      (node (ref "C173") (pin "2") (pinfunction "2_2") (pintype "passive"))
      (node (ref "C174") (pin "1") (pinfunction "1_1") (pintype "passive"))
      (node (ref "C175") (pin "2") (pinfunction "2_2") (pintype "passive"))
      (node (ref "C176") (pin "2") (pinfunction "2_2") (pintype "passive"))
      (node (ref "C177") (pin "1") (pinfunction "1_1") (pintype "passive"))
      (node (ref "C178") (pin "1") (pinfunction "1_1") (pintype "passive"))
      (node (ref "C179") (pin "2") (pinfunction "2_2") (pintype "passive"))
      (node (ref "C180") (pin "2") (pinfunction "2_2") (pintype "passive"))
      (node (ref "C181") (pin "2") (pinfunction "2_2") (pintype "passive"))
      (node (ref "ESD5") (pin "2") (pinfunction "2_2") (pintype "passive"))
      (node (ref "IC10") (pin "16") (pinfunction "DIR2_16") (pintype "passive"))
      (node (ref "IC10") (pin "3") (pinfunction "A3_3") (pintype "passive"))
      (node (ref "IC10") (pin "4") (pinfunction "A4_4") (pintype "passive"))
      (node (ref "IC10") (pin "7") (pinfunction "OE_7") (pintype "passive"))
      (node (ref "IC10") (pin "8") (pinfunction "GND_8") (pintype "passive"))
      (node (ref "IC11") (pin "1") (pinfunction "GND_1") (pintype "passive"))
      (node (ref "IC11") (pin "16") (pinfunction "GND_16") (pintype "passive"))
      (node (ref "IC11") (pin "2") (pinfunction "GND_2") (pintype "passive"))
      (node (ref "IC11") (pin "4") (pinfunction "GND_4") (pintype "passive"))
      (node (ref "IC11") (pin "5") (pinfunction "GND_5") (pintype "passive"))
      (node (ref "IC12") (pin "5") (pinfunction "DIR3_5") (pintype "passive"))
      (node (ref "IC12") (pin "7") (pinfunction "OE_7") (pintype "passive"))
      (node (ref "IC12") (pin "8") (pinfunction "GND_8") (pintype "passive"))
      (node (ref "IC13") (pin "7") (pinfunction "OE_7") (pintype "passive"))
      (node (ref "IC13") (pin "8") (pinfunction "GND_8") (pintype "passive"))
      (node (ref "IC14") (pin "1") (pinfunction "E0_1") (pintype "input"))
      (node (ref "IC14") (pin "2") (pinfunction "E1_2") (pintype "input"))
      (node (ref "IC14") (pin "3") (pinfunction "E2_3") (pintype "input"))
      (node (ref "IC14") (pin "4") (pinfunction "VSS_4") (pintype "power_in"))
      (node (ref "IC14") (pin "7") (pinfunction "~{WC}_7") (pintype "input"))
      (node (ref "IC14") (pin "PAD") (pinfunction "PAD_PAD") (pintype "power_in"))
      (node (ref "IC15") (pin "11") (pinfunction "A0_11") (pintype "input"))
      (node (ref "IC15") (pin "12") (pinfunction "A1_12") (pintype "input"))
      (node (ref "IC15") (pin "13") (pinfunction "A2_13") (pintype "input"))
      (node (ref "IC15") (pin "2") (pinfunction "GPB5_2") (pintype "bidirectional"))
      (node (ref "IC15") (pin "3") (pinfunction "GPB6_3") (pintype "bidirectional"))
      (node (ref "IC15") (pin "6") (pinfunction "VSS_6") (pintype "power_in"))
      (node (ref "IC15") (pin "PAD") (pinfunction "GND_PAD") (pintype "passive"))
      (node (ref "IC8") (pin "16") (pinfunction "DIR2_16") (pintype "passive"))
      (node (ref "IC8") (pin "6") (pinfunction "DIR4_6") (pintype "passive"))
      (node (ref "IC8") (pin "7") (pinfunction "OE_7") (pintype "passive"))
      (node (ref "IC8") (pin "8") (pinfunction "GND_8") (pintype "passive"))
      (node (ref "IC9") (pin "2") (pinfunction "GND_2") (pintype "passive"))
      (node (ref "R120") (pin "2") (pinfunction "2_2") (pintype "passive"))
      (node (ref "R121") (pin "2") (pinfunction "2_2") (pintype "passive"))
      (node (ref "R122") (pin "2") (pinfunction "2_2") (pintype "passive"))
      (node (ref "R123") (pin "2") (pinfunction "2_2") (pintype "passive"))
      (node (ref "R124") (pin "2") (pinfunction "2_2") (pintype "passive"))
      (node (ref "R125") (pin "2") (pinfunction "2_2") (pintype "passive"))
      (node (ref "R126") (pin "2") (pinfunction "2_2") (pintype "passive"))
      (node (ref "R127") (pin "2") (pinfunction "2_2") (pintype "passive"))
      (node (ref "R132") (pin "2") (pinfunction "2_2") (pintype "passive"))
      (node (ref "R135") (pin "1") (pinfunction "1_1") (pintype "passive"))
      (node (ref "R138") (pin "2") (pinfunction "2_2") (pintype "passive"))
      (node (ref "R143") (pin "1") (pinfunction "1_1") (pintype "passive"))
      (node (ref "R146") (pin "1") (pinfunction "1_1") (pintype "passive"))
      (node (ref "X10") (pin "0") (pinfunction "GND_0") (pintype "passive"))
      (node (ref "X10") (pin "15") (pinfunction "GND_15") (pintype "passive"))
      (node (ref "X10") (pin "18") (pinfunction "GND_18") (pintype "passive"))
      (node (ref "X10") (pin "21") (pinfunction "GND_21") (pintype "passive"))
      (node (ref "X10") (pin "26") (pinfunction "GND_26") (pintype "passive"))
      (node (ref "X10") (pin "27") (pinfunction "GND_27") (pintype "passive"))
      (node (ref "X10") (pin "29") (pinfunction "GND_29") (pintype "passive"))
      (node (ref "X10") (pin "34") (pinfunction "GND_34") (pintype "passive"))
      (node (ref "X10") (pin "35") (pinfunction "GND_35") (pintype "passive"))
      (node (ref "X10") (pin "4") (pinfunction "GND_4") (pintype "passive"))
      (node (ref "X10") (pin "40") (pinfunction "GND_40") (pintype "passive"))
      (node (ref "X10") (pin "50") (pinfunction "GND_50") (pintype "passive"))
      (node (ref "X10") (pin "9") (pinfunction "GND_9") (pintype "passive"))
      (node (ref "X5") (pin "2") (pinfunction "Y_2") (pintype "passive"))
      (node (ref "X6") (pin "6") (pinfunction "6_6") (pintype "passive"))
    )
    (net (code "78") (name "Net-(C167-Pad1)") (class "Default")
      (node (ref "C167") (pin "1") (pinfunction "1_1") (pintype "passive"))
      (node (ref "L1") (pin "2") (pinfunction "2_2") (pintype "passive"))
      (node (ref "R107") (pin "1") (pinfunction "1_1") (pintype "passive"))
    )
    (net (code "79") (name "Net-(C170-Pad1)") (class "Default")
      (node (ref "C170") (pin "1") (pinfunction "1_1") (pintype "passive"))
      (node (ref "FR37") (pin "1") (pinfunction "1_1") (pintype "passive"))
      (node (ref "R214") (pin "2") (pinfunction "2_2") (pintype "passive"))
    )
    (net (code "80") (name "Net-(IC11-UART_RX)") (class "Default")
      (node (ref "FR36") (pin "2") (pinfunction "2_2") (pintype "passive"))
      (node (ref "IC11") (pin "9") (pinfunction "UART_RX_9") (pintype "input"))
    )
    (net (code "81") (name "Net-(IC11-UART_TX)") (class "Default")
      (node (ref "FR37") (pin "2") (pinfunction "2_2") (pintype "passive"))
      (node (ref "IC11") (pin "10") (pinfunction "UART_TX_10") (pintype "output"))
    )
    (net (code "82") (name "Net-(LED1-C)") (class "Default")
      (node (ref "LED1") (pin "K") (pinfunction "C_K") (pintype "power_in"))
      (node (ref "R137") (pin "1") (pinfunction "1_1") (pintype "passive"))
    )
    (net (code "83") (name "Net-(LED2-C)") (class "Default")
      (node (ref "LED2") (pin "K") (pinfunction "C_K") (pintype "power_in"))
      (node (ref "R145") (pin "1") (pinfunction "1_1") (pintype "passive"))
    )
    (net (code "84") (name "Net-(R143-Pad2)") (class "Default")
      (node (ref "R143") (pin "2") (pinfunction "2_2") (pintype "passive"))
      (node (ref "X10") (pin "37") (pinfunction "Reserved_37") (pintype "passive"))
    )
    (net (code "85") (name "Net-(R146-Pad2)") (class "Default")
      (node (ref "R146") (pin "2") (pinfunction "2_2") (pintype "passive"))
      (node (ref "X10") (pin "43") (pinfunction "Reserved_43") (pintype "passive"))
    )
    (net (code "86") (name "Net-(R147-Pad2)") (class "Default")
      (node (ref "R147") (pin "2") (pinfunction "2_2") (pintype "passive"))
      (node (ref "X10") (pin "45") (pinfunction "Reserved_45") (pintype "passive"))
    )
    (net (code "87") (name "Net-(X10-SMB_CLK)") (class "Default")
      (node (ref "R136") (pin "1") (pinfunction "1_1") (pintype "passive"))
      (node (ref "R142") (pin "1") (pinfunction "1_1") (pintype "passive"))
      (node (ref "X10") (pin "30") (pinfunction "SMB_CLK_30") (pintype "passive"))
    )
    (net (code "88") (name "Net-(X10-SMB_DATA)") (class "Default")
      (node (ref "R139") (pin "1") (pinfunction "1_1") (pintype "passive"))
      (node (ref "X10") (pin "32") (pinfunction "SMB_DATA_32") (pintype "passive"))
    )
    (net (code "89") (name "VCC1P8") (class "Default")
      (node (ref "C163") (pin "2") (pinfunction "2_2") (pintype "passive"))
      (node (ref "C165") (pin "2") (pinfunction "2_2") (pintype "passive"))
      (node (ref "C172") (pin "2") (pinfunction "2_2") (pintype "passive"))
      (node (ref "C174") (pin "2") (pinfunction "2_2") (pintype "passive"))
      (node (ref "IC10") (pin "14") (pinfunction "VCCA_14") (pintype "passive"))
      (node (ref "IC10") (pin "15") (pinfunction "DIR1_15") (pintype "passive"))
      (node (ref "IC10") (pin "5") (pinfunction "DIR3_5") (pintype "passive"))
      (node (ref "IC10") (pin "6") (pinfunction "DIR4_6") (pintype "passive"))
      (node (ref "IC12") (pin "14") (pinfunction "VCCA_14") (pintype "passive"))
      (node (ref "IC12") (pin "15") (pinfunction "DIR1_15") (pintype "passive"))
      (node (ref "IC12") (pin "16") (pinfunction "DIR2_16") (pintype "passive"))
      (node (ref "IC12") (pin "6") (pinfunction "DIR4_6") (pintype "passive"))
      (node (ref "IC13") (pin "14") (pinfunction "VCCA_14") (pintype "passive"))
      (node (ref "IC13") (pin "15") (pinfunction "DIR1_15") (pintype "passive"))
      (node (ref "IC13") (pin "16") (pinfunction "DIR2_16") (pintype "passive"))
      (node (ref "IC13") (pin "5") (pinfunction "DIR3_5") (pintype "passive"))
      (node (ref "IC13") (pin "6") (pinfunction "DIR4_6") (pintype "passive"))
      (node (ref "IC8") (pin "14") (pinfunction "VCCA_14") (pintype "passive"))
      (node (ref "IC8") (pin "15") (pinfunction "DIR1_15") (pintype "passive"))
      (node (ref "IC8") (pin "5") (pinfunction "DIR3_5") (pintype "passive"))
      (node (ref "R108") (pin "1") (pinfunction "1_1") (pintype "passive"))
      (node (ref "R109") (pin "1") (pinfunction "1_1") (pintype "passive"))
      (node (ref "R110") (pin "1") (pinfunction "1_1") (pintype "passive"))
      (node (ref "R111") (pin "1") (pinfunction "1_1") (pintype "passive"))
      (node (ref "R112") (pin "1") (pinfunction "1_1") (pintype "passive"))
      (node (ref "R113") (pin "1") (pinfunction "1_1") (pintype "passive"))
      (node (ref "R114") (pin "1") (pinfunction "1_1") (pintype "passive"))
      (node (ref "R115") (pin "1") (pinfunction "1_1") (pintype "passive"))
      (node (ref "R116") (pin "1") (pinfunction "1_1") (pintype "passive"))
      (node (ref "R117") (pin "1") (pinfunction "1_1") (pintype "passive"))
      (node (ref "R141") (pin "1") (pinfunction "1_1") (pintype "passive"))
      (node (ref "R148") (pin "1") (pinfunction "1_1") (pintype "passive"))
      (node (ref "VT1") (pin "G") (pinfunction "G_G") (pintype "passive"))
      (node (ref "VT2") (pin "G") (pinfunction "G_G") (pintype "passive"))
    )
    (net (code "90") (name "VCC3P3") (class "Default")
      (node (ref "C164") (pin "1") (pinfunction "1_1") (pintype "passive"))
      (node (ref "C166") (pin "1") (pinfunction "1_1") (pintype "passive"))
      (node (ref "C168") (pin "1") (pinfunction "1_1") (pintype "passive"))
      (node (ref "C173") (pin "1") (pinfunction "1_1") (pintype "passive"))
      (node (ref "C175") (pin "1") (pinfunction "1_1") (pintype "passive"))
      (node (ref "C179") (pin "1") (pinfunction "1_1") (pintype "passive"))
      (node (ref "C181") (pin "1") (pinfunction "1_1") (pintype "passive"))
      (node (ref "IC10") (pin "13") (pinfunction "VCCB_13") (pintype "passive"))
      (node (ref "IC12") (pin "13") (pinfunction "VCCB_13") (pintype "passive"))
      (node (ref "IC13") (pin "13") (pinfunction "VCCB_13") (pintype "passive"))
      (node (ref "IC14") (pin "8") (pinfunction "VCC_8") (pintype "power_in"))
      (node (ref "IC15") (pin "5") (pinfunction "VDD_5") (pintype "power_in"))
      (node (ref "IC8") (pin "13") (pinfunction "VCCB_13") (pintype "passive"))
      (node (ref "IC9") (pin "5") (pinfunction "V+_5") (pintype "power_in"))
      (node (ref "LED1") (pin "A") (pinfunction "A_A") (pintype "power_in"))
      (node (ref "LED2") (pin "A") (pinfunction "A_A") (pintype "power_in"))
      (node (ref "R128") (pin "1") (pinfunction "1_1") (pintype "passive"))
      (node (ref "R140") (pin "1") (pinfunction "1_1") (pintype "passive"))
      (node (ref "R149") (pin "1") (pinfunction "1_1") (pintype "passive"))
      (node (ref "X6") (pin "4") (pinfunction "4_4") (pintype "passive"))
    )
    (net (code "91") (name "VCC3P3_CLK") (class "Default")
      (node (ref "FR38") (pin "1") (pinfunction "1_1") (pintype "passive"))
    )
    (net (code "92") (name "VCC3P3_GNSS") (class "Default")
      (node (ref "C177") (pin "2") (pinfunction "2_2") (pintype "passive"))
      (node (ref "C178") (pin "2") (pinfunction "2_2") (pintype "passive"))
      (node (ref "FR38") (pin "2") (pinfunction "2_2") (pintype "passive"))
      (node (ref "IC11") (pin "14") (pinfunction "BV_14") (pintype "power_in"))
      (node (ref "IC11") (pin "15") (pinfunction "VCC_15") (pintype "power_in"))
      (node (ref "R107") (pin "2") (pinfunction "2_2") (pintype "passive"))
    )
    (net (code "93") (name "VCC3P3_MPCIE") (class "Default")
      (node (ref "R150") (pin "2") (pinfunction "2_2") (pintype "passive"))
      (node (ref "X10") (pin "2") (pinfunction "+3.3V_2") (pintype "passive"))
      (node (ref "X10") (pin "52") (pinfunction "+3.3V_52") (pintype "passive"))
    )
    (net (code "94") (name "unconnected-(IC9-ALERT-Pad3)") (class "Default")
      (node (ref "IC9") (pin "3") (pinfunction "ALERT_3") (pintype "output+no_connect"))
    )
    (net (code "95") (name "unconnected-(IC10-B3-Pad10)") (class "Default")
      (node (ref "IC10") (pin "10") (pinfunction "B3_10") (pintype "passive+no_connect"))
    )
    (net (code "96") (name "unconnected-(IC10-B4-Pad9)") (class "Default")
      (node (ref "IC10") (pin "9") (pinfunction "B4_9") (pintype "passive+no_connect"))
    )
    (net (code "97") (name "unconnected-(IC11-E2-Pad11)") (class "Default")
      (node (ref "IC11") (pin "11") (pinfunction "E2_11") (pintype "passive+no_connect"))
    )
    (net (code "98") (name "unconnected-(IC11-E3-Pad12)") (class "Default")
      (node (ref "IC11") (pin "12") (pinfunction "E3_12") (pintype "passive+no_connect"))
    )
    (net (code "99") (name "unconnected-(IC15-INTA-Pad16)") (class "Default")
      (node (ref "IC15") (pin "16") (pinfunction "INTA_16") (pintype "open_collector+no_connect"))
    )
    (net (code "100") (name "unconnected-(IC15-INTB-Pad15)") (class "Default")
      (node (ref "IC15") (pin "15") (pinfunction "INTB_15") (pintype "open_collector+no_connect"))
    )
    (net (code "101") (name "unconnected-(IC15-NC-Pad7)") (class "Default")
      (node (ref "IC15") (pin "7") (pinfunction "NC_7") (pintype "passive+no_connect"))
    )
    (net (code "102") (name "unconnected-(IC15-NC-Pad10)") (class "Default")
      (node (ref "IC15") (pin "10") (pinfunction "NC_10") (pintype "passive+no_connect"))
    )
    (net (code "103") (name "unconnected-(X10-+1.5V-Pad6)") (class "Default")
      (node (ref "X10") (pin "6") (pinfunction "+1.5V_6") (pintype "passive+no_connect"))
    )
    (net (code "104") (name "unconnected-(X10-+1.5V-Pad28)") (class "Default")
      (node (ref "X10") (pin "28") (pinfunction "+1.5V_28") (pintype "passive+no_connect"))
    )
    (net (code "105") (name "unconnected-(X10-+1.5V-Pad48)") (class "Default")
      (node (ref "X10") (pin "48") (pinfunction "+1.5V_48") (pintype "passive+no_connect"))
    )
    (net (code "106") (name "unconnected-(X10-+3.3Vaux-Pad24)") (class "Default")
      (node (ref "X10") (pin "24") (pinfunction "+3.3Vaux_24") (pintype "passive+no_connect"))
    )
    (net (code "107") (name "unconnected-(X10-UIM_CLK-Pad12)") (class "Default")
      (node (ref "X10") (pin "12") (pinfunction "UIM_CLK_12") (pintype "passive+no_connect"))
    )
    (net (code "108") (name "unconnected-(X10-UIM_DATA-Pad10)") (class "Default")
      (node (ref "X10") (pin "10") (pinfunction "UIM_DATA_10") (pintype "passive+no_connect"))
    )
    (net (code "109") (name "unconnected-(X10-UIM_PWR-Pad8)") (class "Default")
      (node (ref "X10") (pin "8") (pinfunction "UIM_PWR_8") (pintype "passive+no_connect"))
    )
    (net (code "110") (name "unconnected-(X10-UIM_RESET-Pad14)") (class "Default")
      (node (ref "X10") (pin "14") (pinfunction "UIM_RESET_14") (pintype "passive+no_connect"))
    )
    (net (code "111") (name "unconnected-(X10-UIM_VPP-Pad16)") (class "Default")
      (node (ref "X10") (pin "16") (pinfunction "UIM_VPP_16") (pintype "passive+no_connect"))
    )
    (net (code "112") (name "unconnected-(X10-USB_DM-Pad36)") (class "Default")
      (node (ref "X10") (pin "36") (pinfunction "USB_DM_36") (pintype "passive+no_connect"))
    )
    (net (code "113") (name "unconnected-(X10-USB_DP-Pad38)") (class "Default")
      (node (ref "X10") (pin "38") (pinfunction "USB_DP_38") (pintype "passive+no_connect"))
    )
    (net (code "114") (name "unconnected-(X10-WAKE#-Pad1)") (class "Default")
      (node (ref "X10") (pin "1") (pinfunction "WAKE#_1") (pintype "passive+no_connect"))
    )
  )
)
